# backplate_final_rev02.net
KiCad netlist of a schematic drawn in EAGLE
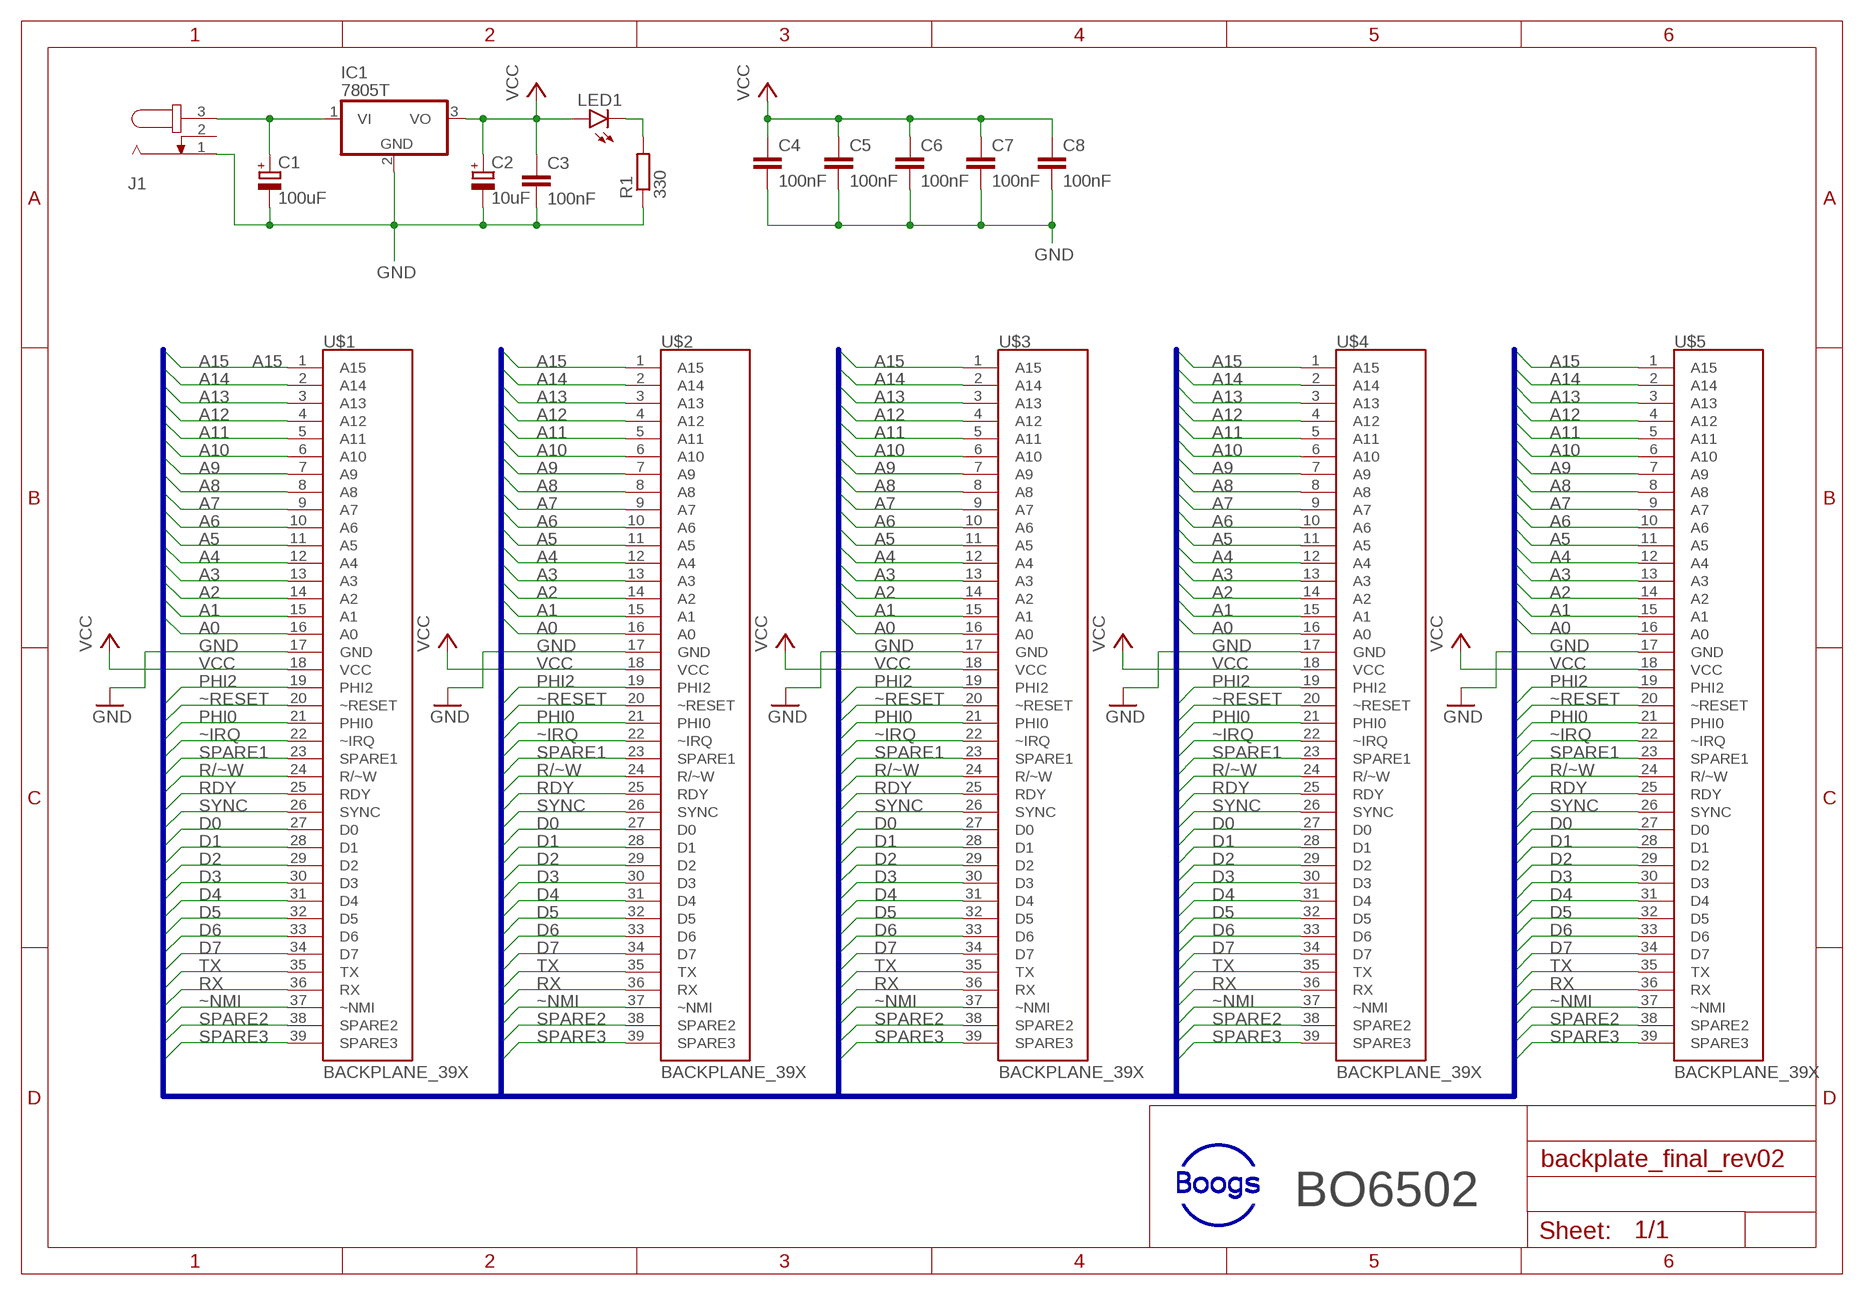
[diagram p0: schematic, sheet 1]

(export (version "E")
  (design (tool "Eeschema 10.0.6"))
  (components
    (comp (ref "C1")
      (value "100uF")
      (footprint "eagle-import:B45181A")
      (libsource (lib "eagle-import") (part "CPOL-EUB45181A"))
    )
    (comp (ref "C2")
      (value "10uF")
      (footprint "eagle-import:B45181A")
      (libsource (lib "eagle-import") (part "CPOL-EUB45181A"))
    )
    (comp (ref "C3")
      (value "100nF")
      (footprint "eagle-import:C025-025X050")
      (libsource (lib "eagle-import") (part "C-EU025-025X050"))
    )
    (comp (ref "C4")
      (value "100nF")
      (footprint "eagle-import:C025-025X050")
      (libsource (lib "eagle-import") (part "C-EU025-025X050"))
    )
    (comp (ref "C5")
      (value "100nF")
      (footprint "eagle-import:C025-025X050")
      (libsource (lib "eagle-import") (part "C-EU025-025X050"))
    )
    (comp (ref "C6")
      (value "100nF")
      (footprint "eagle-import:C025-025X050")
      (libsource (lib "eagle-import") (part "C-EU025-025X050"))
    )
    (comp (ref "C7")
      (value "100nF")
      (footprint "eagle-import:C025-025X050")
      (libsource (lib "eagle-import") (part "C-EU025-025X050"))
    )
    (comp (ref "C8")
      (value "100nF")
      (footprint "eagle-import:C025-025X050")
      (libsource (lib "eagle-import") (part "C-EU025-025X050"))
    )
    (comp (ref "IC1")
      (value "7805T")
      (footprint "eagle-import:TO220H")
      (libsource (lib "eagle-import") (part "78T05"))
    )
    (comp (ref "J1")
      (value "JACK-PLUG1")
      (footprint "eagle-import:SPC4078")
      (libsource (lib "eagle-import") (part "JACK-PLUG1"))
    )
    (comp (ref "LED1")
      (value "LED5MM")
      (footprint "eagle-import:LED5MM")
      (libsource (lib "eagle-import") (part "LED5MM"))
    )
    (comp (ref "R1")
      (value "330")
      (footprint "eagle-import:0207_10")
      (libsource (lib "eagle-import") (part "R-EU_0207/10"))
    )
    (comp (ref "U$1")
      (value "BACKPLANE_39X")
      (footprint "eagle-import:BP_39X")
      (fields (field (name "A15") "A15"))
      (libsource (lib "eagle-import") (part "BACKPLANE_39X"))
    )
    (comp (ref "U$2")
      (value "BACKPLANE_39X")
      (footprint "eagle-import:BP_39X")
      (libsource (lib "eagle-import") (part "BACKPLANE_39X"))
    )
    (comp (ref "U$3")
      (value "BACKPLANE_39X")
      (footprint "eagle-import:BP_39X")
      (libsource (lib "eagle-import") (part "BACKPLANE_39X"))
    )
    (comp (ref "U$4")
      (value "BACKPLANE_39X")
      (footprint "eagle-import:BP_39X")
      (libsource (lib "eagle-import") (part "BACKPLANE_39X"))
    )
    (comp (ref "U$5")
      (value "BACKPLANE_39X")
      (footprint "eagle-import:BP_39X")
      (libsource (lib "eagle-import") (part "BACKPLANE_39X"))
    )
  )
  (nets
    (net (code "1") (name "/A0") (class "Default")
      (node (ref "U$1") (pin "16") (pinfunction "A0_16") (pintype "bidirectional"))
      (node (ref "U$2") (pin "16") (pinfunction "A0_16") (pintype "bidirectional"))
      (node (ref "U$3") (pin "16") (pinfunction "A0_16") (pintype "bidirectional"))
      (node (ref "U$4") (pin "16") (pinfunction "A0_16") (pintype "bidirectional"))
      (node (ref "U$5") (pin "16") (pinfunction "A0_16") (pintype "bidirectional"))
    )
    (net (code "2") (name "/A1") (class "Default")
      (node (ref "U$1") (pin "15") (pinfunction "A1_15") (pintype "bidirectional"))
      (node (ref "U$2") (pin "15") (pinfunction "A1_15") (pintype "bidirectional"))
      (node (ref "U$3") (pin "15") (pinfunction "A1_15") (pintype "bidirectional"))
      (node (ref "U$4") (pin "15") (pinfunction "A1_15") (pintype "bidirectional"))
      (node (ref "U$5") (pin "15") (pinfunction "A1_15") (pintype "bidirectional"))
    )
    (net (code "3") (name "/A2") (class "Default")
      (node (ref "U$1") (pin "14") (pinfunction "A2_14") (pintype "bidirectional"))
      (node (ref "U$2") (pin "14") (pinfunction "A2_14") (pintype "bidirectional"))
      (node (ref "U$3") (pin "14") (pinfunction "A2_14") (pintype "bidirectional"))
      (node (ref "U$4") (pin "14") (pinfunction "A2_14") (pintype "bidirectional"))
      (node (ref "U$5") (pin "14") (pinfunction "A2_14") (pintype "bidirectional"))
    )
    (net (code "4") (name "/A3") (class "Default")
      (node (ref "U$1") (pin "13") (pinfunction "A3_13") (pintype "bidirectional"))
      (node (ref "U$2") (pin "13") (pinfunction "A3_13") (pintype "bidirectional"))
      (node (ref "U$3") (pin "13") (pinfunction "A3_13") (pintype "bidirectional"))
      (node (ref "U$4") (pin "13") (pinfunction "A3_13") (pintype "bidirectional"))
      (node (ref "U$5") (pin "13") (pinfunction "A3_13") (pintype "bidirectional"))
    )
    (net (code "5") (name "/A4") (class "Default")
      (node (ref "U$1") (pin "12") (pinfunction "A4_12") (pintype "bidirectional"))
      (node (ref "U$2") (pin "12") (pinfunction "A4_12") (pintype "bidirectional"))
      (node (ref "U$3") (pin "12") (pinfunction "A4_12") (pintype "bidirectional"))
      (node (ref "U$4") (pin "12") (pinfunction "A4_12") (pintype "bidirectional"))
      (node (ref "U$5") (pin "12") (pinfunction "A4_12") (pintype "bidirectional"))
    )
    (net (code "6") (name "/A5") (class "Default")
      (node (ref "U$1") (pin "11") (pinfunction "A5_11") (pintype "bidirectional"))
      (node (ref "U$2") (pin "11") (pinfunction "A5_11") (pintype "bidirectional"))
      (node (ref "U$3") (pin "11") (pinfunction "A5_11") (pintype "bidirectional"))
      (node (ref "U$4") (pin "11") (pinfunction "A5_11") (pintype "bidirectional"))
      (node (ref "U$5") (pin "11") (pinfunction "A5_11") (pintype "bidirectional"))
    )
    (net (code "7") (name "/A6") (class "Default")
      (node (ref "U$1") (pin "10") (pinfunction "A6_10") (pintype "bidirectional"))
      (node (ref "U$2") (pin "10") (pinfunction "A6_10") (pintype "bidirectional"))
      (node (ref "U$3") (pin "10") (pinfunction "A6_10") (pintype "bidirectional"))
      (node (ref "U$4") (pin "10") (pinfunction "A6_10") (pintype "bidirectional"))
      (node (ref "U$5") (pin "10") (pinfunction "A6_10") (pintype "bidirectional"))
    )
    (net (code "8") (name "/A7") (class "Default")
      (node (ref "U$1") (pin "9") (pinfunction "A7_9") (pintype "bidirectional"))
      (node (ref "U$2") (pin "9") (pinfunction "A7_9") (pintype "bidirectional"))
      (node (ref "U$3") (pin "9") (pinfunction "A7_9") (pintype "bidirectional"))
      (node (ref "U$4") (pin "9") (pinfunction "A7_9") (pintype "bidirectional"))
      (node (ref "U$5") (pin "9") (pinfunction "A7_9") (pintype "bidirectional"))
    )
    (net (code "9") (name "/A8") (class "Default")
      (node (ref "U$1") (pin "8") (pinfunction "A8_8") (pintype "bidirectional"))
      (node (ref "U$2") (pin "8") (pinfunction "A8_8") (pintype "bidirectional"))
      (node (ref "U$3") (pin "8") (pinfunction "A8_8") (pintype "bidirectional"))
      (node (ref "U$4") (pin "8") (pinfunction "A8_8") (pintype "bidirectional"))
      (node (ref "U$5") (pin "8") (pinfunction "A8_8") (pintype "bidirectional"))
    )
    (net (code "10") (name "/A9") (class "Default")
      (node (ref "U$1") (pin "7") (pinfunction "A9_7") (pintype "bidirectional"))
      (node (ref "U$2") (pin "7") (pinfunction "A9_7") (pintype "bidirectional"))
      (node (ref "U$3") (pin "7") (pinfunction "A9_7") (pintype "bidirectional"))
      (node (ref "U$4") (pin "7") (pinfunction "A9_7") (pintype "bidirectional"))
      (node (ref "U$5") (pin "7") (pinfunction "A9_7") (pintype "bidirectional"))
    )
    (net (code "11") (name "/A10") (class "Default")
      (node (ref "U$1") (pin "6") (pinfunction "A10_6") (pintype "bidirectional"))
      (node (ref "U$2") (pin "6") (pinfunction "A10_6") (pintype "bidirectional"))
      (node (ref "U$3") (pin "6") (pinfunction "A10_6") (pintype "bidirectional"))
      (node (ref "U$4") (pin "6") (pinfunction "A10_6") (pintype "bidirectional"))
      (node (ref "U$5") (pin "6") (pinfunction "A10_6") (pintype "bidirectional"))
    )
    (net (code "12") (name "/A11") (class "Default")
      (node (ref "U$1") (pin "5") (pinfunction "A11_5") (pintype "bidirectional"))
      (node (ref "U$2") (pin "5") (pinfunction "A11_5") (pintype "bidirectional"))
      (node (ref "U$3") (pin "5") (pinfunction "A11_5") (pintype "bidirectional"))
      (node (ref "U$4") (pin "5") (pinfunction "A11_5") (pintype "bidirectional"))
      (node (ref "U$5") (pin "5") (pinfunction "A11_5") (pintype "bidirectional"))
    )
    (net (code "13") (name "/A12") (class "Default")
      (node (ref "U$1") (pin "4") (pinfunction "A12_4") (pintype "bidirectional"))
      (node (ref "U$2") (pin "4") (pinfunction "A12_4") (pintype "bidirectional"))
      (node (ref "U$3") (pin "4") (pinfunction "A12_4") (pintype "bidirectional"))
      (node (ref "U$4") (pin "4") (pinfunction "A12_4") (pintype "bidirectional"))
      (node (ref "U$5") (pin "4") (pinfunction "A12_4") (pintype "bidirectional"))
    )
    (net (code "14") (name "/A13") (class "Default")
      (node (ref "U$1") (pin "3") (pinfunction "A13_3") (pintype "bidirectional"))
      (node (ref "U$2") (pin "3") (pinfunction "A13_3") (pintype "bidirectional"))
      (node (ref "U$3") (pin "3") (pinfunction "A13_3") (pintype "bidirectional"))
      (node (ref "U$4") (pin "3") (pinfunction "A13_3") (pintype "bidirectional"))
      (node (ref "U$5") (pin "3") (pinfunction "A13_3") (pintype "bidirectional"))
    )
    (net (code "15") (name "/A14") (class "Default")
      (node (ref "U$1") (pin "2") (pinfunction "A14_2") (pintype "bidirectional"))
      (node (ref "U$2") (pin "2") (pinfunction "A14_2") (pintype "bidirectional"))
      (node (ref "U$3") (pin "2") (pinfunction "A14_2") (pintype "bidirectional"))
      (node (ref "U$4") (pin "2") (pinfunction "A14_2") (pintype "bidirectional"))
      (node (ref "U$5") (pin "2") (pinfunction "A14_2") (pintype "bidirectional"))
    )
    (net (code "16") (name "/A15") (class "Default")
      (node (ref "U$1") (pin "1") (pinfunction "A15_1") (pintype "bidirectional"))
      (node (ref "U$2") (pin "1") (pinfunction "A15_1") (pintype "bidirectional"))
      (node (ref "U$3") (pin "1") (pinfunction "A15_1") (pintype "bidirectional"))
      (node (ref "U$4") (pin "1") (pinfunction "A15_1") (pintype "bidirectional"))
      (node (ref "U$5") (pin "1") (pinfunction "A15_1") (pintype "bidirectional"))
    )
    (net (code "17") (name "/D0") (class "Default")
      (node (ref "U$1") (pin "27") (pinfunction "D0_27") (pintype "bidirectional"))
      (node (ref "U$2") (pin "27") (pinfunction "D0_27") (pintype "bidirectional"))
      (node (ref "U$3") (pin "27") (pinfunction "D0_27") (pintype "bidirectional"))
      (node (ref "U$4") (pin "27") (pinfunction "D0_27") (pintype "bidirectional"))
      (node (ref "U$5") (pin "27") (pinfunction "D0_27") (pintype "bidirectional"))
    )
    (net (code "18") (name "/D1") (class "Default")
      (node (ref "U$1") (pin "28") (pinfunction "D1_28") (pintype "bidirectional"))
      (node (ref "U$2") (pin "28") (pinfunction "D1_28") (pintype "bidirectional"))
      (node (ref "U$3") (pin "28") (pinfunction "D1_28") (pintype "bidirectional"))
      (node (ref "U$4") (pin "28") (pinfunction "D1_28") (pintype "bidirectional"))
      (node (ref "U$5") (pin "28") (pinfunction "D1_28") (pintype "bidirectional"))
    )
    (net (code "19") (name "/D2") (class "Default")
      (node (ref "U$1") (pin "29") (pinfunction "D2_29") (pintype "bidirectional"))
      (node (ref "U$2") (pin "29") (pinfunction "D2_29") (pintype "bidirectional"))
      (node (ref "U$3") (pin "29") (pinfunction "D2_29") (pintype "bidirectional"))
      (node (ref "U$4") (pin "29") (pinfunction "D2_29") (pintype "bidirectional"))
      (node (ref "U$5") (pin "29") (pinfunction "D2_29") (pintype "bidirectional"))
    )
    (net (code "20") (name "/D3") (class "Default")
      (node (ref "U$1") (pin "30") (pinfunction "D3_30") (pintype "bidirectional"))
      (node (ref "U$2") (pin "30") (pinfunction "D3_30") (pintype "bidirectional"))
      (node (ref "U$3") (pin "30") (pinfunction "D3_30") (pintype "bidirectional"))
      (node (ref "U$4") (pin "30") (pinfunction "D3_30") (pintype "bidirectional"))
      (node (ref "U$5") (pin "30") (pinfunction "D3_30") (pintype "bidirectional"))
    )
    (net (code "21") (name "/D4") (class "Default")
      (node (ref "U$1") (pin "31") (pinfunction "D4_31") (pintype "bidirectional"))
      (node (ref "U$2") (pin "31") (pinfunction "D4_31") (pintype "bidirectional"))
      (node (ref "U$3") (pin "31") (pinfunction "D4_31") (pintype "bidirectional"))
      (node (ref "U$4") (pin "31") (pinfunction "D4_31") (pintype "bidirectional"))
      (node (ref "U$5") (pin "31") (pinfunction "D4_31") (pintype "bidirectional"))
    )
    (net (code "22") (name "/D5") (class "Default")
      (node (ref "U$1") (pin "32") (pinfunction "D5_32") (pintype "bidirectional"))
      (node (ref "U$2") (pin "32") (pinfunction "D5_32") (pintype "bidirectional"))
      (node (ref "U$3") (pin "32") (pinfunction "D5_32") (pintype "bidirectional"))
      (node (ref "U$4") (pin "32") (pinfunction "D5_32") (pintype "bidirectional"))
      (node (ref "U$5") (pin "32") (pinfunction "D5_32") (pintype "bidirectional"))
    )
    (net (code "23") (name "/D6") (class "Default")
      (node (ref "U$1") (pin "33") (pinfunction "D6_33") (pintype "bidirectional"))
      (node (ref "U$2") (pin "33") (pinfunction "D6_33") (pintype "bidirectional"))
      (node (ref "U$3") (pin "33") (pinfunction "D6_33") (pintype "bidirectional"))
      (node (ref "U$4") (pin "33") (pinfunction "D6_33") (pintype "bidirectional"))
      (node (ref "U$5") (pin "33") (pinfunction "D6_33") (pintype "bidirectional"))
    )
    (net (code "24") (name "/D7") (class "Default")
      (node (ref "U$1") (pin "34") (pinfunction "D7_34") (pintype "bidirectional"))
      (node (ref "U$2") (pin "34") (pinfunction "D7_34") (pintype "bidirectional"))
      (node (ref "U$3") (pin "34") (pinfunction "D7_34") (pintype "bidirectional"))
      (node (ref "U$4") (pin "34") (pinfunction "D7_34") (pintype "bidirectional"))
      (node (ref "U$5") (pin "34") (pinfunction "D7_34") (pintype "bidirectional"))
    )
    (net (code "25") (name "/PHI0") (class "Default")
      (node (ref "U$1") (pin "21") (pinfunction "PHI0_21") (pintype "bidirectional"))
      (node (ref "U$2") (pin "21") (pinfunction "PHI0_21") (pintype "bidirectional"))
      (node (ref "U$3") (pin "21") (pinfunction "PHI0_21") (pintype "bidirectional"))
      (node (ref "U$4") (pin "21") (pinfunction "PHI0_21") (pintype "bidirectional"))
      (node (ref "U$5") (pin "21") (pinfunction "PHI0_21") (pintype "bidirectional"))
    )
    (net (code "26") (name "/PHI2") (class "Default")
      (node (ref "U$1") (pin "19") (pinfunction "PHI2_19") (pintype "bidirectional"))
      (node (ref "U$2") (pin "19") (pinfunction "PHI2_19") (pintype "bidirectional"))
      (node (ref "U$3") (pin "19") (pinfunction "PHI2_19") (pintype "bidirectional"))
      (node (ref "U$4") (pin "19") (pinfunction "PHI2_19") (pintype "bidirectional"))
      (node (ref "U$5") (pin "19") (pinfunction "PHI2_19") (pintype "bidirectional"))
    )
    (net (code "27") (name "/RDY") (class "Default")
      (node (ref "U$1") (pin "25") (pinfunction "RDY_25") (pintype "bidirectional"))
      (node (ref "U$2") (pin "25") (pinfunction "RDY_25") (pintype "bidirectional"))
      (node (ref "U$3") (pin "25") (pinfunction "RDY_25") (pintype "bidirectional"))
      (node (ref "U$4") (pin "25") (pinfunction "RDY_25") (pintype "bidirectional"))
      (node (ref "U$5") (pin "25") (pinfunction "RDY_25") (pintype "bidirectional"))
    )
    (net (code "28") (name "/RX") (class "Default")
      (node (ref "U$1") (pin "36") (pinfunction "RX_36") (pintype "bidirectional"))
      (node (ref "U$2") (pin "36") (pinfunction "RX_36") (pintype "bidirectional"))
      (node (ref "U$3") (pin "36") (pinfunction "RX_36") (pintype "bidirectional"))
      (node (ref "U$4") (pin "36") (pinfunction "RX_36") (pintype "bidirectional"))
      (node (ref "U$5") (pin "36") (pinfunction "RX_36") (pintype "bidirectional"))
    )
    (net (code "29") (name "/R{slash}~{W}") (class "Default")
      (node (ref "U$1") (pin "24") (pinfunction "R/~{W}_24") (pintype "bidirectional"))
      (node (ref "U$2") (pin "24") (pinfunction "R/~{W}_24") (pintype "bidirectional"))
      (node (ref "U$3") (pin "24") (pinfunction "R/~{W}_24") (pintype "bidirectional"))
      (node (ref "U$4") (pin "24") (pinfunction "R/~{W}_24") (pintype "bidirectional"))
      (node (ref "U$5") (pin "24") (pinfunction "R/~{W}_24") (pintype "bidirectional"))
    )
    (net (code "30") (name "/SPARE1") (class "Default")
      (node (ref "U$1") (pin "23") (pinfunction "SPARE1_23") (pintype "bidirectional"))
      (node (ref "U$2") (pin "23") (pinfunction "SPARE1_23") (pintype "bidirectional"))
      (node (ref "U$3") (pin "23") (pinfunction "SPARE1_23") (pintype "bidirectional"))
      (node (ref "U$4") (pin "23") (pinfunction "SPARE1_23") (pintype "bidirectional"))
      (node (ref "U$5") (pin "23") (pinfunction "SPARE1_23") (pintype "bidirectional"))
    )
    (net (code "31") (name "/SPARE2") (class "Default")
      (node (ref "U$1") (pin "38") (pinfunction "SPARE2_38") (pintype "bidirectional"))
      (node (ref "U$2") (pin "38") (pinfunction "SPARE2_38") (pintype "bidirectional"))
      (node (ref "U$3") (pin "38") (pinfunction "SPARE2_38") (pintype "bidirectional"))
      (node (ref "U$4") (pin "38") (pinfunction "SPARE2_38") (pintype "bidirectional"))
      (node (ref "U$5") (pin "38") (pinfunction "SPARE2_38") (pintype "bidirectional"))
    )
    (net (code "32") (name "/SPARE3") (class "Default")
      (node (ref "U$1") (pin "39") (pinfunction "SPARE3_39") (pintype "bidirectional"))
      (node (ref "U$2") (pin "39") (pinfunction "SPARE3_39") (pintype "bidirectional"))
      (node (ref "U$3") (pin "39") (pinfunction "SPARE3_39") (pintype "bidirectional"))
      (node (ref "U$4") (pin "39") (pinfunction "SPARE3_39") (pintype "bidirectional"))
      (node (ref "U$5") (pin "39") (pinfunction "SPARE3_39") (pintype "bidirectional"))
    )
    (net (code "33") (name "/SYNC") (class "Default")
      (node (ref "U$1") (pin "26") (pinfunction "SYNC_26") (pintype "bidirectional"))
      (node (ref "U$2") (pin "26") (pinfunction "SYNC_26") (pintype "bidirectional"))
      (node (ref "U$3") (pin "26") (pinfunction "SYNC_26") (pintype "bidirectional"))
      (node (ref "U$4") (pin "26") (pinfunction "SYNC_26") (pintype "bidirectional"))
      (node (ref "U$5") (pin "26") (pinfunction "SYNC_26") (pintype "bidirectional"))
    )
    (net (code "34") (name "/TX") (class "Default")
      (node (ref "U$1") (pin "35") (pinfunction "TX_35") (pintype "bidirectional"))
      (node (ref "U$2") (pin "35") (pinfunction "TX_35") (pintype "bidirectional"))
      (node (ref "U$3") (pin "35") (pinfunction "TX_35") (pintype "bidirectional"))
      (node (ref "U$4") (pin "35") (pinfunction "TX_35") (pintype "bidirectional"))
      (node (ref "U$5") (pin "35") (pinfunction "TX_35") (pintype "bidirectional"))
    )
    (net (code "35") (name "/~{IRQ}") (class "Default")
      (node (ref "U$1") (pin "22") (pinfunction "~{IRQ}_22") (pintype "bidirectional"))
      (node (ref "U$2") (pin "22") (pinfunction "~{IRQ}_22") (pintype "bidirectional"))
      (node (ref "U$3") (pin "22") (pinfunction "~{IRQ}_22") (pintype "bidirectional"))
      (node (ref "U$4") (pin "22") (pinfunction "~{IRQ}_22") (pintype "bidirectional"))
      (node (ref "U$5") (pin "22") (pinfunction "~{IRQ}_22") (pintype "bidirectional"))
    )
    (net (code "36") (name "/~{NMI}") (class "Default")
      (node (ref "U$1") (pin "37") (pinfunction "~{NMI}_37") (pintype "bidirectional"))
      (node (ref "U$2") (pin "37") (pinfunction "~{NMI}_37") (pintype "bidirectional"))
      (node (ref "U$3") (pin "37") (pinfunction "~{NMI}_37") (pintype "bidirectional"))
      (node (ref "U$4") (pin "37") (pinfunction "~{NMI}_37") (pintype "bidirectional"))
      (node (ref "U$5") (pin "37") (pinfunction "~{NMI}_37") (pintype "bidirectional"))
    )
    (net (code "37") (name "/~{RESET}") (class "Default")
      (node (ref "U$1") (pin "20") (pinfunction "~{RESET}_20") (pintype "bidirectional"))
      (node (ref "U$2") (pin "20") (pinfunction "~{RESET}_20") (pintype "bidirectional"))
      (node (ref "U$3") (pin "20") (pinfunction "~{RESET}_20") (pintype "bidirectional"))
      (node (ref "U$4") (pin "20") (pinfunction "~{RESET}_20") (pintype "bidirectional"))
      (node (ref "U$5") (pin "20") (pinfunction "~{RESET}_20") (pintype "bidirectional"))
    )
    (net (code "38") (name "GND") (class "Default")
      (node (ref "C1") (pin "-") (pinfunction "-_-") (pintype "passive"))
      (node (ref "C2") (pin "-") (pinfunction "-_-") (pintype "passive"))
      (node (ref "C3") (pin "2") (pinfunction "2_2") (pintype "passive"))
      (node (ref "C4") (pin "2") (pinfunction "2_2") (pintype "passive"))
      (node (ref "C5") (pin "2") (pinfunction "2_2") (pintype "passive"))
      (node (ref "C6") (pin "2") (pinfunction "2_2") (pintype "passive"))
      (node (ref "C7") (pin "2") (pinfunction "2_2") (pintype "passive"))
      (node (ref "C8") (pin "2") (pinfunction "2_2") (pintype "passive"))
      (node (ref "IC1") (pin "2") (pinfunction "GND_2") (pintype "passive"))
      (node (ref "J1") (pin "1") (pinfunction "1_1") (pintype "passive"))
      (node (ref "R1") (pin "1") (pinfunction "1_1") (pintype "passive"))
      (node (ref "U$1") (pin "17") (pinfunction "GND_17") (pintype "bidirectional"))
      (node (ref "U$2") (pin "17") (pinfunction "GND_17") (pintype "bidirectional"))
      (node (ref "U$3") (pin "17") (pinfunction "GND_17") (pintype "bidirectional"))
      (node (ref "U$4") (pin "17") (pinfunction "GND_17") (pintype "bidirectional"))
      (node (ref "U$5") (pin "17") (pinfunction "GND_17") (pintype "bidirectional"))
    )
    (net (code "39") (name "Net-(IC1-VI)") (class "Default")
      (node (ref "C1") (pin "+") (pinfunction "+_+") (pintype "passive"))
      (node (ref "IC1") (pin "1") (pinfunction "VI_1") (pintype "input"))
      (node (ref "J1") (pin "3") (pinfunction "3_3") (pintype "passive"))
    )
    (net (code "40") (name "Net-(LED1-C)") (class "Default")
      (node (ref "LED1") (pin "K") (pinfunction "C_K") (pintype "passive"))
      (node (ref "R1") (pin "2") (pinfunction "2_2") (pintype "passive"))
    )
    (net (code "41") (name "VCC") (class "Default")
      (node (ref "C2") (pin "+") (pinfunction "+_+") (pintype "passive"))
      (node (ref "C3") (pin "1") (pinfunction "1_1") (pintype "passive"))
      (node (ref "C4") (pin "1") (pinfunction "1_1") (pintype "passive"))
      (node (ref "C5") (pin "1") (pinfunction "1_1") (pintype "passive"))
      (node (ref "C6") (pin "1") (pinfunction "1_1") (pintype "passive"))
      (node (ref "C7") (pin "1") (pinfunction "1_1") (pintype "passive"))
      (node (ref "C8") (pin "1") (pinfunction "1_1") (pintype "passive"))
      (node (ref "IC1") (pin "3") (pinfunction "VO_3") (pintype "passive"))
      (node (ref "LED1") (pin "A") (pinfunction "A_A") (pintype "passive"))
      (node (ref "U$1") (pin "18") (pinfunction "VCC_18") (pintype "bidirectional"))
      (node (ref "U$2") (pin "18") (pinfunction "VCC_18") (pintype "bidirectional"))
      (node (ref "U$3") (pin "18") (pinfunction "VCC_18") (pintype "bidirectional"))
      (node (ref "U$4") (pin "18") (pinfunction "VCC_18") (pintype "bidirectional"))
      (node (ref "U$5") (pin "18") (pinfunction "VCC_18") (pintype "bidirectional"))
    )
    (net (code "42") (name "unconnected-(J1-Pad2)") (class "Default")
      (node (ref "J1") (pin "2") (pinfunction "2_2") (pintype "passive"))
    )
  )
)
